# SCH_AP-Controller_Sheet_1_Altium.net
KiCad netlist of a schematic drawn in Altium Designer
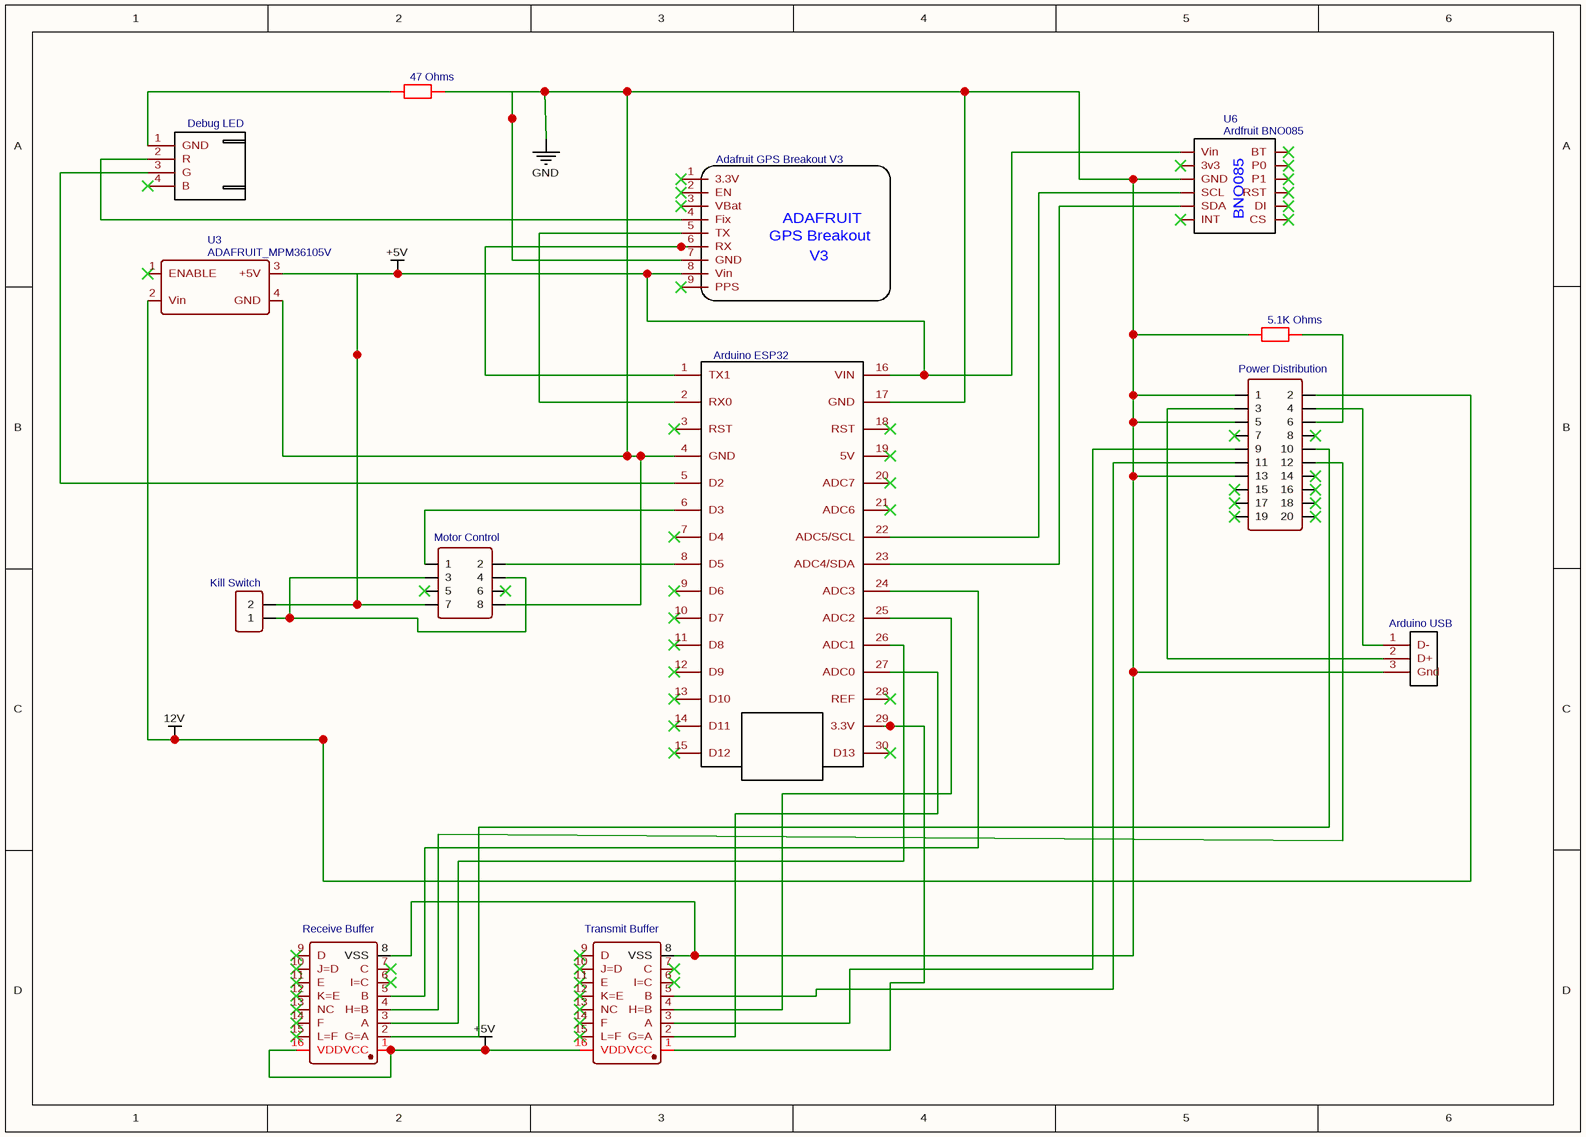
[diagram p0: SCH_AP-Controller_Sheet_1_Altium.schdoc]

(export (version "E")
  (design (tool "Eeschema 10.0.6"))
  (components
    (comp (ref "HDR-M-2.54_2X4")
      (value "Motor Control")
      (fields (field (name "CONTRIBUTOR") "LCEDA_Lib"))
      (libsource (lib "altium-import") (part "root_0_Motor Control_"))
    )
    (comp (ref "JST-XH-4-PIN")
      (value "Debug LED")
      (fields (field (name "CONTRIBUTOR") "loyboy"))
      (libsource (lib "altium-import") (part "root_0_Debug LED_"))
    )
    (comp (ref "JST_XH2.54_2P")
      (value "Kill Switch")
      (fields (field (name "MANUFACTURER PART") "JST_XH2.54_2P") (field (name "CONTRIBUTOR") "Андрей Скиффи"))
      (libsource (lib "altium-import") (part "root_0_Kill Switch_"))
    )
    (comp (ref "JST_XH_1X3")
      (value "Arduino USB")
      (fields (field (name "CONTRIBUTOR") "GeMeMe"))
      (libsource (lib "altium-import") (part "root_0_Arduino USB_"))
    )
    (comp (ref "POWER1")
      (value "Power Distribution")
      (fields (field (name "CONTRIBUTOR") "LCEDA_Lib"))
      (libsource (lib "altium-import") (part "root_0_Power Distribution_"))
    )
    (comp (ref "R1")
      (value "47 Ohms")
      (fields (field (name "CONTRIBUTOR") "Kagutsuchi"))
      (libsource (lib "altium-import") (part "root_0_47 Ohms_"))
    )
    (comp (ref "R2")
      (value "5.1K Ohms")
      (fields (field (name "CONTRIBUTOR") "Kagutsuchi"))
      (libsource (lib "altium-import") (part "root_0_5.1K Ohms_"))
    )
    (comp (ref "U1")
      (value "Arduino ESP32")
      (fields (field (name "CONTRIBUTOR") "Nikolay Yanev"))
      (libsource (lib "altium-import") (part "root_0_Arduino ESP32_"))
    )
    (comp (ref "U2")
      (value "Transmit Buffer")
      (fields
        (field (name "MANUFACTURER") "TI(德州仪器)")
        (field (name "MANUFACTURER PART") "CD4010BE")
        (field (name "CONTRIBUTOR") "LCSC")
      )
      (libsource (lib "altium-import") (part "root_2_Transmit Buffer_"))
    )
    (comp (ref "U3")
      (value "ADAFRUIT_MPM36105V")
      (fields (field (name "CONTRIBUTOR") "Aidan Farley"))
      (libsource (lib "altium-import") (part "root_0_ADAFRUIT_MPM36105V_"))
    )
    (comp (ref "U4")
      (value "Adafruit GPS Breakout V3")
      (fields (field (name "MANUFACTURER PART") "New SchematicLib") (field (name "CONTRIBUTOR") "NiklasC"))
      (libsource (lib "altium-import") (part "root_0_Adafruit GPS Breakout V3_"))
    )
    (comp (ref "U5")
      (value "Receive Buffer")
      (fields
        (field (name "MANUFACTURER") "TI(德州仪器)")
        (field (name "MANUFACTURER PART") "CD4010BE")
        (field (name "CONTRIBUTOR") "LCSC")
      )
      (libsource (lib "altium-import") (part "root_2_Receive Buffer_"))
    )
    (comp (ref "U6")
      (value "Ardfruit BNO085")
      (fields (field (name "MANUFACTURER") "Ardfruit") (field (name "CONTRIBUTOR") "Ashok Dhaker"))
      (libsource (lib "altium-import") (part "root_0_Ardfruit BNO085_"))
    )
  )
  (nets
    (net (code "1") (name "+5V") (class "Default")
      (node (ref "HDR-M-2.54_2X4") (pin "7") (pinfunction "7_7") (pintype "passive"))
      (node (ref "JST_XH2.54_2P") (pin "2") (pinfunction "2_2") (pintype "passive"))
      (node (ref "U1") (pin "16") (pinfunction "VIN_16") (pintype "passive"))
      (node (ref "U2") (pin "16") (pinfunction "VDD_16") (pintype "passive"))
      (node (ref "U3") (pin "3") (pinfunction "+5V_3") (pintype "passive"))
      (node (ref "U4") (pin "8") (pinfunction "Vin_8") (pintype "passive"))
      (node (ref "U5") (pin "1") (pinfunction "VCC_1") (pintype "passive"))
      (node (ref "U5") (pin "16") (pinfunction "VDD_16") (pintype "passive"))
      (node (ref "U6") (pin "1") (pinfunction "Vin_1") (pintype "passive"))
    )
    (net (code "2") (name "12V") (class "Default")
      (node (ref "POWER1") (pin "2") (pinfunction "2_2") (pintype "passive"))
      (node (ref "U3") (pin "2") (pinfunction "Vin_2") (pintype "passive"))
    )
    (net (code "3") (name "GND") (class "Default")
      (node (ref "HDR-M-2.54_2X4") (pin "8") (pinfunction "8_8") (pintype "passive"))
      (node (ref "JST_XH_1X3") (pin "3") (pinfunction "Gnd_3") (pintype "passive"))
      (node (ref "POWER1") (pin "1") (pinfunction "1_1") (pintype "passive"))
      (node (ref "POWER1") (pin "13") (pinfunction "13_13") (pintype "passive"))
      (node (ref "POWER1") (pin "5") (pinfunction "5_5") (pintype "passive"))
      (node (ref "R1") (pin "2") (pinfunction "1_2") (pintype "passive"))
      (node (ref "R2") (pin "1") (pinfunction "2_1") (pintype "passive"))
      (node (ref "U1") (pin "17") (pinfunction "GND_17") (pintype "passive"))
      (node (ref "U1") (pin "4") (pinfunction "GND_4") (pintype "passive"))
      (node (ref "U2") (pin "8") (pinfunction "VSS_8") (pintype "passive"))
      (node (ref "U3") (pin "4") (pinfunction "GND_4") (pintype "passive"))
      (node (ref "U4") (pin "7") (pinfunction "GND_7") (pintype "passive"))
      (node (ref "U5") (pin "8") (pinfunction "VSS_8") (pintype "passive"))
      (node (ref "U6") (pin "3") (pinfunction "GND_3") (pintype "passive"))
    )
    (net (code "4") (name "Net-(HDR-M-2.54_2X4-Pad3)") (class "Default")
      (node (ref "HDR-M-2.54_2X4") (pin "3") (pinfunction "3_3") (pintype "passive"))
      (node (ref "HDR-M-2.54_2X4") (pin "4") (pinfunction "4_4") (pintype "passive"))
      (node (ref "JST_XH2.54_2P") (pin "1") (pinfunction "1_1") (pintype "passive"))
    )
    (net (code "5") (name "Net-(JST-XH-4-PIN-G)") (class "Default")
      (node (ref "JST-XH-4-PIN") (pin "3") (pinfunction "G_3") (pintype "passive"))
      (node (ref "U1") (pin "5") (pinfunction "D2_5") (pintype "passive"))
    )
    (net (code "6") (name "Net-(JST-XH-4-PIN-GND)") (class "Default")
      (node (ref "JST-XH-4-PIN") (pin "1") (pinfunction "GND_1") (pintype "passive"))
      (node (ref "R1") (pin "1") (pinfunction "2_1") (pintype "passive"))
    )
    (net (code "7") (name "Net-(JST-XH-4-PIN-R)") (class "Default")
      (node (ref "JST-XH-4-PIN") (pin "2") (pinfunction "R_2") (pintype "passive"))
      (node (ref "U4") (pin "4") (pinfunction "Fix_4") (pintype "passive"))
    )
    (net (code "8") (name "Net-(JST_XH_1X3-D+)") (class "Default")
      (node (ref "JST_XH_1X3") (pin "2") (pinfunction "D+_2") (pintype "passive"))
      (node (ref "POWER1") (pin "3") (pinfunction "3_3") (pintype "passive"))
    )
    (net (code "9") (name "Net-(JST_XH_1X3-D-)") (class "Default")
      (node (ref "JST_XH_1X3") (pin "1") (pinfunction "D-_1") (pintype "passive"))
      (node (ref "POWER1") (pin "4") (pinfunction "4_4") (pintype "passive"))
    )
    (net (code "10") (name "Net-(R2-1)") (class "Default")
      (node (ref "POWER1") (pin "6") (pinfunction "6_6") (pintype "passive"))
      (node (ref "R2") (pin "2") (pinfunction "1_2") (pintype "passive"))
    )
    (net (code "11") (name "Net-(U1-3.3V)") (class "Default")
      (node (ref "U1") (pin "29") (pinfunction "3.3V_29") (pintype "passive"))
      (node (ref "U2") (pin "1") (pinfunction "VCC_1") (pintype "passive"))
    )
    (net (code "12") (name "Net-(U1-ADC0)") (class "Default")
      (node (ref "U1") (pin "27") (pinfunction "ADC0_27") (pintype "passive"))
      (node (ref "U2") (pin "2") (pinfunction "G=A_2") (pintype "passive"))
    )
    (net (code "13") (name "Net-(U1-ADC1)") (class "Default")
      (node (ref "U1") (pin "26") (pinfunction "ADC1_26") (pintype "passive"))
      (node (ref "U5") (pin "3") (pinfunction "A_3") (pintype "passive"))
    )
    (net (code "14") (name "Net-(U1-ADC2)") (class "Default")
      (node (ref "U1") (pin "25") (pinfunction "ADC2_25") (pintype "passive"))
      (node (ref "U2") (pin "4") (pinfunction "H=B_4") (pintype "passive"))
    )
    (net (code "15") (name "Net-(U1-ADC3)") (class "Default")
      (node (ref "U1") (pin "24") (pinfunction "ADC3_24") (pintype "passive"))
      (node (ref "U5") (pin "5") (pinfunction "B_5") (pintype "passive"))
    )
    (net (code "16") (name "Net-(U1-ADC4{slash}SDA)") (class "Default")
      (node (ref "U1") (pin "23") (pinfunction "ADC4/SDA_23") (pintype "passive"))
      (node (ref "U6") (pin "5") (pinfunction "SDA_5") (pintype "passive"))
    )
    (net (code "17") (name "Net-(U1-ADC5{slash}SCL)") (class "Default")
      (node (ref "U1") (pin "22") (pinfunction "ADC5/SCL_22") (pintype "passive"))
      (node (ref "U6") (pin "4") (pinfunction "SCL_4") (pintype "passive"))
    )
    (net (code "18") (name "Net-(U1-D3)") (class "Default")
      (node (ref "HDR-M-2.54_2X4") (pin "1") (pinfunction "1_1") (pintype "passive"))
      (node (ref "U1") (pin "6") (pinfunction "D3_6") (pintype "passive"))
    )
    (net (code "19") (name "Net-(U1-D5)") (class "Default")
      (node (ref "HDR-M-2.54_2X4") (pin "2") (pinfunction "2_2") (pintype "passive"))
      (node (ref "U1") (pin "8") (pinfunction "D5_8") (pintype "passive"))
    )
    (net (code "20") (name "Net-(U1-RX0)") (class "Default")
      (node (ref "U1") (pin "2") (pinfunction "RX0_2") (pintype "passive"))
      (node (ref "U4") (pin "5") (pinfunction "TX_5") (pintype "passive"))
    )
    (net (code "21") (name "Net-(U1-TX1)") (class "Default")
      (node (ref "U1") (pin "1") (pinfunction "TX1_1") (pintype "passive"))
      (node (ref "U4") (pin "6") (pinfunction "RX_6") (pintype "passive"))
    )
    (net (code "22") (name "Net-(U2-A)") (class "Default")
      (node (ref "POWER1") (pin "9") (pinfunction "9_9") (pintype "passive"))
      (node (ref "U2") (pin "3") (pinfunction "A_3") (pintype "passive"))
    )
    (net (code "23") (name "Net-(U2-B)") (class "Default")
      (node (ref "POWER1") (pin "11") (pinfunction "11_11") (pintype "passive"))
      (node (ref "U2") (pin "5") (pinfunction "B_5") (pintype "passive"))
    )
    (net (code "24") (name "Net-(U5-G=A)") (class "Default")
      (node (ref "POWER1") (pin "10") (pinfunction "10_10") (pintype "passive"))
      (node (ref "U5") (pin "2") (pinfunction "G=A_2") (pintype "passive"))
    )
    (net (code "25") (name "Net-(U5-H=B)") (class "Default")
      (node (ref "POWER1") (pin "12") (pinfunction "12_12") (pintype "passive"))
      (node (ref "U5") (pin "4") (pinfunction "H=B_4") (pintype "passive"))
    )
    (net (code "26") (name "unconnected-(HDR-M-2.54_2X4-Pad5)") (class "Default")
      (node (ref "HDR-M-2.54_2X4") (pin "5") (pinfunction "5_5") (pintype "passive+no_connect"))
    )
    (net (code "27") (name "unconnected-(HDR-M-2.54_2X4-Pad6)") (class "Default")
      (node (ref "HDR-M-2.54_2X4") (pin "6") (pinfunction "6_6") (pintype "passive+no_connect"))
    )
    (net (code "28") (name "unconnected-(JST-XH-4-PIN-B-Pad4)") (class "Default")
      (node (ref "JST-XH-4-PIN") (pin "4") (pinfunction "B_4") (pintype "passive+no_connect"))
    )
    (net (code "29") (name "unconnected-(POWER1-Pad7)") (class "Default")
      (node (ref "POWER1") (pin "7") (pinfunction "7_7") (pintype "passive+no_connect"))
    )
    (net (code "30") (name "unconnected-(POWER1-Pad8)") (class "Default")
      (node (ref "POWER1") (pin "8") (pinfunction "8_8") (pintype "passive+no_connect"))
    )
    (net (code "31") (name "unconnected-(POWER1-Pad14)") (class "Default")
      (node (ref "POWER1") (pin "14") (pinfunction "14_14") (pintype "passive+no_connect"))
    )
    (net (code "32") (name "unconnected-(POWER1-Pad15)") (class "Default")
      (node (ref "POWER1") (pin "15") (pinfunction "15_15") (pintype "passive+no_connect"))
    )
    (net (code "33") (name "unconnected-(POWER1-Pad16)") (class "Default")
      (node (ref "POWER1") (pin "16") (pinfunction "16_16") (pintype "passive+no_connect"))
    )
    (net (code "34") (name "unconnected-(POWER1-Pad17)") (class "Default")
      (node (ref "POWER1") (pin "17") (pinfunction "17_17") (pintype "passive+no_connect"))
    )
    (net (code "35") (name "unconnected-(POWER1-Pad18)") (class "Default")
      (node (ref "POWER1") (pin "18") (pinfunction "18_18") (pintype "passive+no_connect"))
    )
    (net (code "36") (name "unconnected-(POWER1-Pad19)") (class "Default")
      (node (ref "POWER1") (pin "19") (pinfunction "19_19") (pintype "passive+no_connect"))
    )
    (net (code "37") (name "unconnected-(POWER1-Pad20)") (class "Default")
      (node (ref "POWER1") (pin "20") (pinfunction "20_20") (pintype "passive+no_connect"))
    )
    (net (code "38") (name "unconnected-(U1-5V-Pad19)") (class "Default")
      (node (ref "U1") (pin "19") (pinfunction "5V_19") (pintype "passive+no_connect"))
    )
    (net (code "39") (name "unconnected-(U1-ADC6-Pad21)") (class "Default")
      (node (ref "U1") (pin "21") (pinfunction "ADC6_21") (pintype "passive+no_connect"))
    )
    (net (code "40") (name "unconnected-(U1-ADC7-Pad20)") (class "Default")
      (node (ref "U1") (pin "20") (pinfunction "ADC7_20") (pintype "passive+no_connect"))
    )
    (net (code "41") (name "unconnected-(U1-D4-Pad7)") (class "Default")
      (node (ref "U1") (pin "7") (pinfunction "D4_7") (pintype "passive+no_connect"))
    )
    (net (code "42") (name "unconnected-(U1-D6-Pad9)") (class "Default")
      (node (ref "U1") (pin "9") (pinfunction "D6_9") (pintype "passive+no_connect"))
    )
    (net (code "43") (name "unconnected-(U1-D7-Pad10)") (class "Default")
      (node (ref "U1") (pin "10") (pinfunction "D7_10") (pintype "passive+no_connect"))
    )
    (net (code "44") (name "unconnected-(U1-D8-Pad11)") (class "Default")
      (node (ref "U1") (pin "11") (pinfunction "D8_11") (pintype "passive+no_connect"))
    )
    (net (code "45") (name "unconnected-(U1-D9-Pad12)") (class "Default")
      (node (ref "U1") (pin "12") (pinfunction "D9_12") (pintype "passive+no_connect"))
    )
    (net (code "46") (name "unconnected-(U1-D10-Pad13)") (class "Default")
      (node (ref "U1") (pin "13") (pinfunction "D10_13") (pintype "passive+no_connect"))
    )
    (net (code "47") (name "unconnected-(U1-D11-Pad14)") (class "Default")
      (node (ref "U1") (pin "14") (pinfunction "D11_14") (pintype "passive+no_connect"))
    )
    (net (code "48") (name "unconnected-(U1-D12-Pad15)") (class "Default")
      (node (ref "U1") (pin "15") (pinfunction "D12_15") (pintype "passive+no_connect"))
    )
    (net (code "49") (name "unconnected-(U1-D13-Pad30)") (class "Default")
      (node (ref "U1") (pin "30") (pinfunction "D13_30") (pintype "passive+no_connect"))
    )
    (net (code "50") (name "unconnected-(U1-REF-Pad28)") (class "Default")
      (node (ref "U1") (pin "28") (pinfunction "REF_28") (pintype "passive+no_connect"))
    )
    (net (code "51") (name "unconnected-(U1-RST-Pad3)") (class "Default")
      (node (ref "U1") (pin "3") (pinfunction "RST_3") (pintype "passive+no_connect"))
    )
    (net (code "52") (name "unconnected-(U1-RST-Pad18)") (class "Default")
      (node (ref "U1") (pin "18") (pinfunction "RST_18") (pintype "passive+no_connect"))
    )
    (net (code "53") (name "unconnected-(U2-C-Pad7)") (class "Default")
      (node (ref "U2") (pin "7") (pinfunction "C_7") (pintype "passive+no_connect"))
    )
    (net (code "54") (name "unconnected-(U2-D-Pad9)") (class "Default")
      (node (ref "U2") (pin "9") (pinfunction "D_9") (pintype "passive+no_connect"))
    )
    (net (code "55") (name "unconnected-(U2-E-Pad11)") (class "Default")
      (node (ref "U2") (pin "11") (pinfunction "E_11") (pintype "passive+no_connect"))
    )
    (net (code "56") (name "unconnected-(U2-F-Pad14)") (class "Default")
      (node (ref "U2") (pin "14") (pinfunction "F_14") (pintype "passive+no_connect"))
    )
    (net (code "57") (name "unconnected-(U2-I=C-Pad6)") (class "Default")
      (node (ref "U2") (pin "6") (pinfunction "I=C_6") (pintype "passive+no_connect"))
    )
    (net (code "58") (name "unconnected-(U2-J=D-Pad10)") (class "Default")
      (node (ref "U2") (pin "10") (pinfunction "J=D_10") (pintype "passive+no_connect"))
    )
    (net (code "59") (name "unconnected-(U2-K=E-Pad12)") (class "Default")
      (node (ref "U2") (pin "12") (pinfunction "K=E_12") (pintype "passive+no_connect"))
    )
    (net (code "60") (name "unconnected-(U2-L=F-Pad15)") (class "Default")
      (node (ref "U2") (pin "15") (pinfunction "L=F_15") (pintype "passive+no_connect"))
    )
    (net (code "61") (name "unconnected-(U2-NC-Pad13)") (class "Default")
      (node (ref "U2") (pin "13") (pinfunction "NC_13") (pintype "passive+no_connect"))
    )
    (net (code "62") (name "unconnected-(U3-ENABLE-Pad1)") (class "Default")
      (node (ref "U3") (pin "1") (pinfunction "ENABLE_1") (pintype "passive+no_connect"))
    )
    (net (code "63") (name "unconnected-(U4-3.3V-Pad1)") (class "Default")
      (node (ref "U4") (pin "1") (pinfunction "3.3V_1") (pintype "passive+no_connect"))
    )
    (net (code "64") (name "unconnected-(U4-EN-Pad2)") (class "Default")
      (node (ref "U4") (pin "2") (pinfunction "EN_2") (pintype "passive+no_connect"))
    )
    (net (code "65") (name "unconnected-(U4-PPS-Pad9)") (class "Default")
      (node (ref "U4") (pin "9") (pinfunction "PPS_9") (pintype "passive+no_connect"))
    )
    (net (code "66") (name "unconnected-(U4-VBat-Pad3)") (class "Default")
      (node (ref "U4") (pin "3") (pinfunction "VBat_3") (pintype "passive+no_connect"))
    )
    (net (code "67") (name "unconnected-(U5-C-Pad7)") (class "Default")
      (node (ref "U5") (pin "7") (pinfunction "C_7") (pintype "passive+no_connect"))
    )
    (net (code "68") (name "unconnected-(U5-D-Pad9)") (class "Default")
      (node (ref "U5") (pin "9") (pinfunction "D_9") (pintype "passive+no_connect"))
    )
    (net (code "69") (name "unconnected-(U5-E-Pad11)") (class "Default")
      (node (ref "U5") (pin "11") (pinfunction "E_11") (pintype "passive+no_connect"))
    )
    (net (code "70") (name "unconnected-(U5-F-Pad14)") (class "Default")
      (node (ref "U5") (pin "14") (pinfunction "F_14") (pintype "passive+no_connect"))
    )
    (net (code "71") (name "unconnected-(U5-I=C-Pad6)") (class "Default")
      (node (ref "U5") (pin "6") (pinfunction "I=C_6") (pintype "passive+no_connect"))
    )
    (net (code "72") (name "unconnected-(U5-J=D-Pad10)") (class "Default")
      (node (ref "U5") (pin "10") (pinfunction "J=D_10") (pintype "passive+no_connect"))
    )
    (net (code "73") (name "unconnected-(U5-K=E-Pad12)") (class "Default")
      (node (ref "U5") (pin "12") (pinfunction "K=E_12") (pintype "passive+no_connect"))
    )
    (net (code "74") (name "unconnected-(U5-L=F-Pad15)") (class "Default")
      (node (ref "U5") (pin "15") (pinfunction "L=F_15") (pintype "passive+no_connect"))
    )
    (net (code "75") (name "unconnected-(U5-NC-Pad13)") (class "Default")
      (node (ref "U5") (pin "13") (pinfunction "NC_13") (pintype "passive+no_connect"))
    )
    (net (code "76") (name "unconnected-(U6-3v3-Pad2)") (class "Default")
      (node (ref "U6") (pin "2") (pinfunction "3v3_2") (pintype "passive+no_connect"))
    )
    (net (code "77") (name "unconnected-(U6-BT-Pad12)") (class "Default")
      (node (ref "U6") (pin "12") (pinfunction "BT_12") (pintype "passive+no_connect"))
    )
    (net (code "78") (name "unconnected-(U6-CS-Pad7)") (class "Default")
      (node (ref "U6") (pin "7") (pinfunction "CS_7") (pintype "passive+no_connect"))
    )
    (net (code "79") (name "unconnected-(U6-DI-Pad8)") (class "Default")
      (node (ref "U6") (pin "8") (pinfunction "DI_8") (pintype "passive+no_connect"))
    )
    (net (code "80") (name "unconnected-(U6-INT-Pad6)") (class "Default")
      (node (ref "U6") (pin "6") (pinfunction "INT_6") (pintype "passive+no_connect"))
    )
    (net (code "81") (name "unconnected-(U6-P0-Pad11)") (class "Default")
      (node (ref "U6") (pin "11") (pinfunction "P0_11") (pintype "passive+no_connect"))
    )
    (net (code "82") (name "unconnected-(U6-P1-Pad10)") (class "Default")
      (node (ref "U6") (pin "10") (pinfunction "P1_10") (pintype "passive+no_connect"))
    )
    (net (code "83") (name "unconnected-(U6-RST-Pad9)") (class "Default")
      (node (ref "U6") (pin "9") (pinfunction "RST_9") (pintype "passive+no_connect"))
    )
  )
)
